# Actuators.net
KiCad netlist of a schematic drawn in Altium Designer
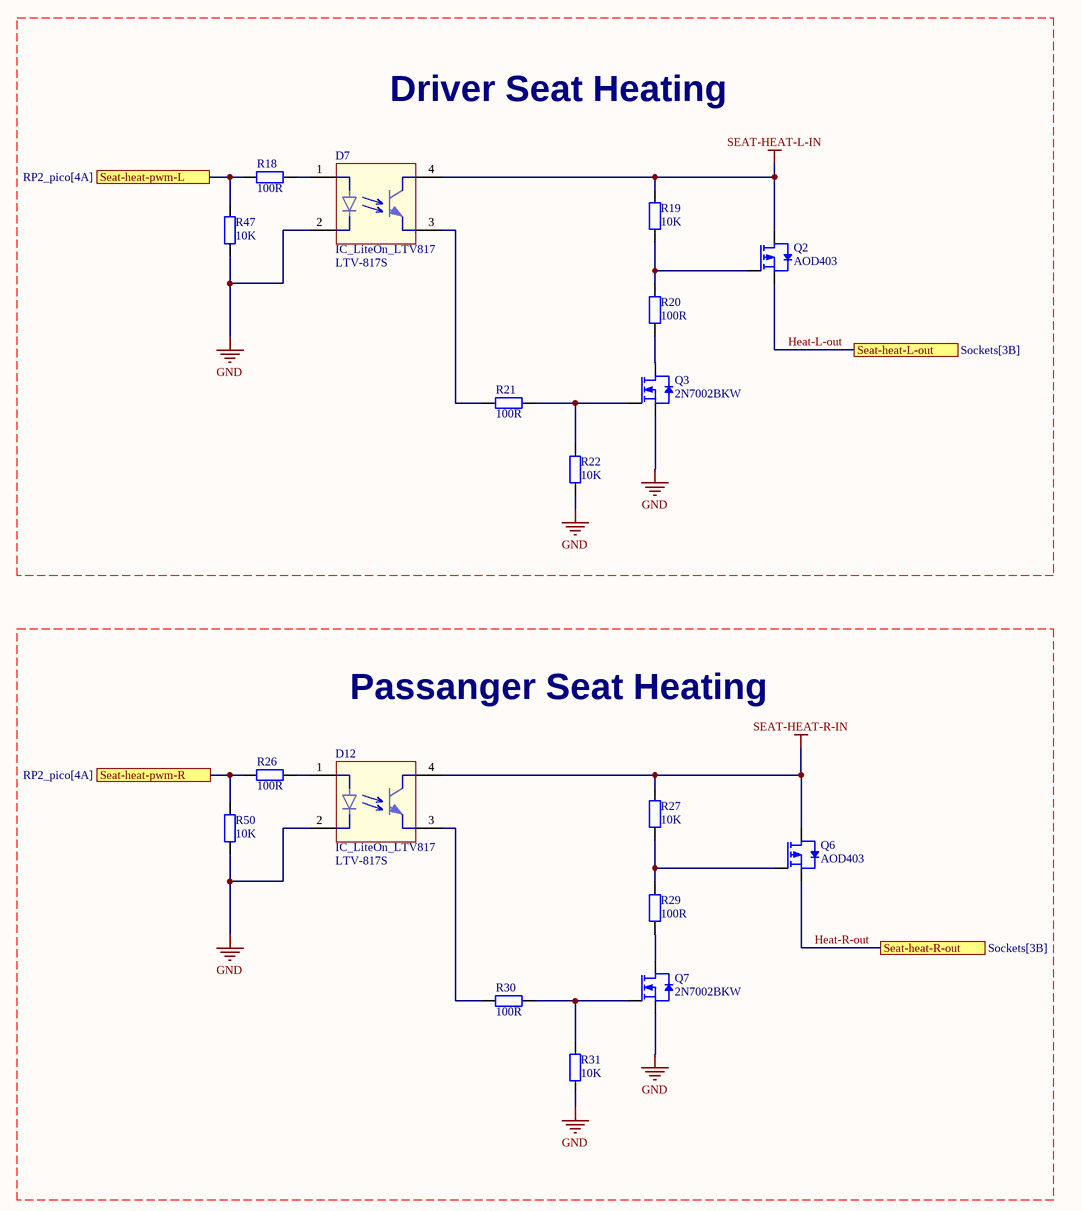
[diagram p0: Actuators.SchDoc, left]
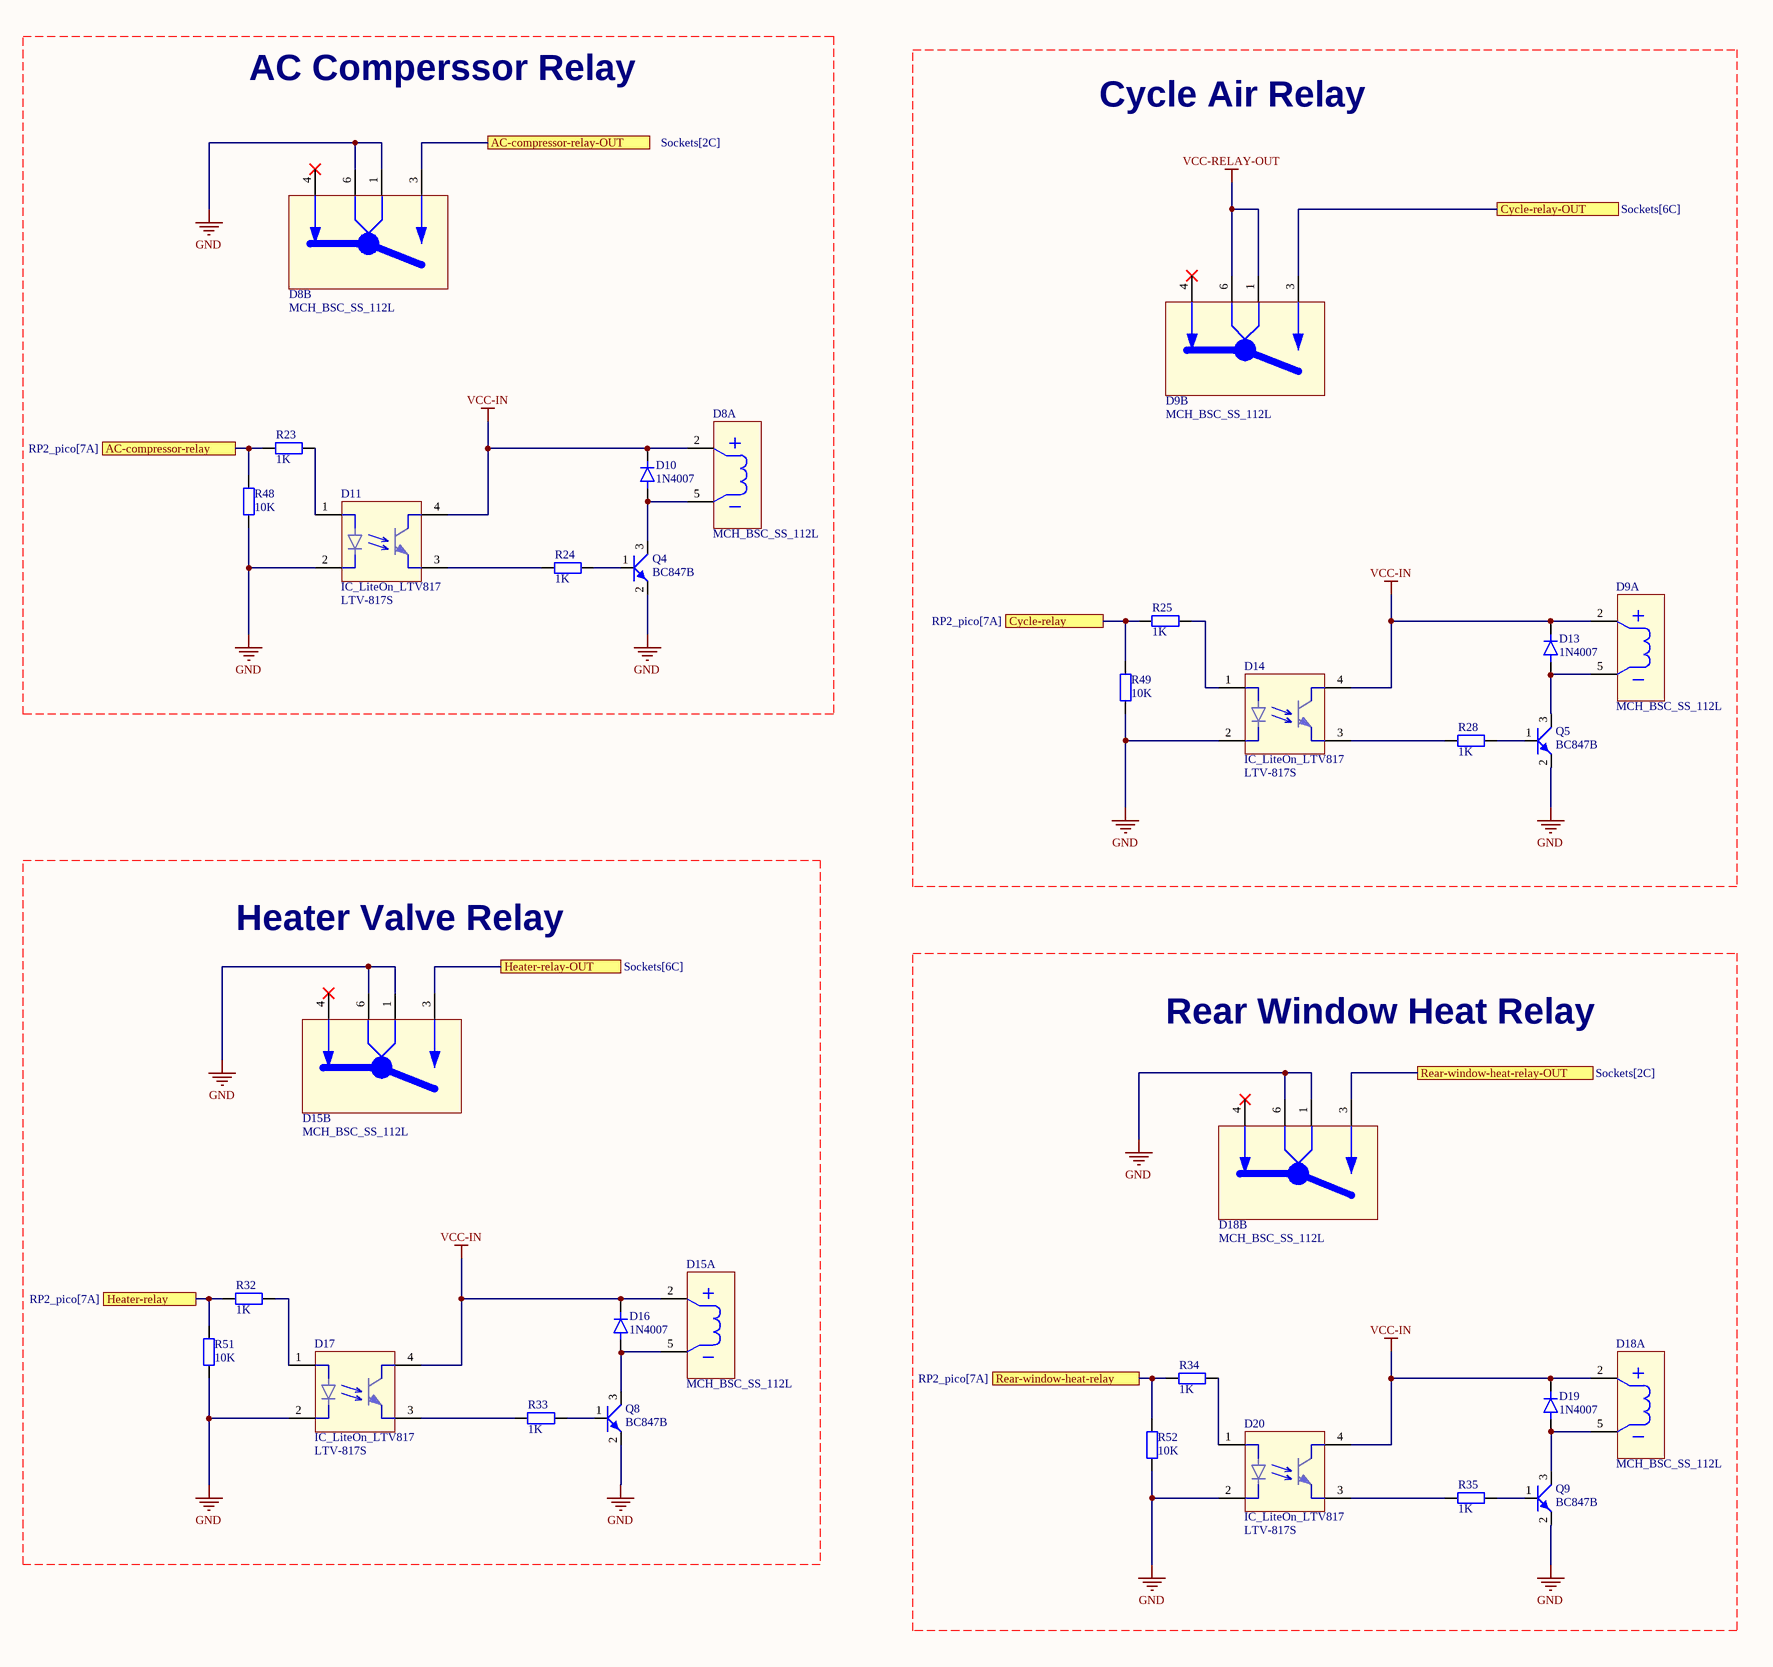
[diagram p1: Actuators.SchDoc, right]

(export (version "E")
  (design (tool "Eeschema 10.0.6"))
  (components
    (comp (ref "D7")
      (value "IC_LiteOn_LTV817")
      (footprint "IC_LiteOn_ LTV-817S")
      (description "Transistor Output Optocouplers Optocoupler Phototrans")
      (fields (field (name "VALUE1") "LTV-817S") (field (name "MANUFACTURER") "Lite-On"))
      (libsource (lib "DSW_Lib") (part "IC_LiteOn_LTV817"))
    )
    (comp (ref "D8")
      (value "MCH_BSC_SS_112L")
      (footprint "MCH_BSC_SS_112L")
      (description "Small relay 6 pins 12V, 2A")
      (fields (field (name "MANUFACTURER") "KJS"))
      (libsource (lib "") (part "MCH_BSC_SS_112L_1"))
    )
    (comp (ref "D9")
      (value "MCH_BSC_SS_112L")
      (footprint "MCH_BSC_SS_112L")
      (description "Small relay 6 pins 12V, 2A")
      (fields (field (name "MANUFACTURER") "KJS"))
      (libsource (lib "") (part "MCH_BSC_SS_112L_2"))
    )
    (comp (ref "D10")
      (value "DIO")
      (footprint "DO-214AC")
      (description "M7 Diode, max 30A")
      (fields (field (name "VALUE1") "1N4007"))
      (libsource (lib "DSW_Lib") (part "DIO"))
    )
    (comp (ref "D11")
      (value "IC_LiteOn_LTV817")
      (footprint "IC_LiteOn_ LTV-817S")
      (description "Transistor Output Optocouplers Optocoupler Phototrans")
      (fields (field (name "VALUE1") "LTV-817S") (field (name "MANUFACTURER") "Lite-On"))
      (libsource (lib "DSW_Lib") (part "IC_LiteOn_LTV817"))
    )
    (comp (ref "D12")
      (value "IC_LiteOn_LTV817")
      (footprint "IC_LiteOn_ LTV-817S")
      (description "Transistor Output Optocouplers Optocoupler Phototrans")
      (fields (field (name "VALUE1") "LTV-817S") (field (name "MANUFACTURER") "Lite-On"))
      (libsource (lib "DSW_Lib") (part "IC_LiteOn_LTV817"))
    )
    (comp (ref "D13")
      (value "DIO")
      (footprint "DO-214AC")
      (description "M7 Diode, max 30A")
      (fields (field (name "VALUE1") "1N4007"))
      (libsource (lib "DSW_Lib") (part "DIO"))
    )
    (comp (ref "D14")
      (value "IC_LiteOn_LTV817")
      (footprint "IC_LiteOn_ LTV-817S")
      (description "Transistor Output Optocouplers Optocoupler Phototrans")
      (fields (field (name "VALUE1") "LTV-817S") (field (name "MANUFACTURER") "Lite-On"))
      (libsource (lib "DSW_Lib") (part "IC_LiteOn_LTV817"))
    )
    (comp (ref "D15")
      (value "MCH_BSC_SS_112L")
      (footprint "MCH_BSC_SS_112L")
      (description "Small relay 6 pins 12V, 2A")
      (fields (field (name "MANUFACTURER") "KJS"))
      (libsource (lib "DSW_Lib") (part "MCH_BSC_SS_112L"))
    )
    (comp (ref "D16")
      (value "DIO")
      (footprint "DO-214AC")
      (description "M7 Diode, max 30A")
      (fields (field (name "VALUE1") "1N4007"))
      (libsource (lib "DSW_Lib") (part "DIO"))
    )
    (comp (ref "D17")
      (value "IC_LiteOn_LTV817")
      (footprint "IC_LiteOn_ LTV-817S")
      (description "Transistor Output Optocouplers Optocoupler Phototrans")
      (fields (field (name "VALUE1") "LTV-817S") (field (name "MANUFACTURER") "Lite-On"))
      (libsource (lib "DSW_Lib") (part "IC_LiteOn_LTV817"))
    )
    (comp (ref "D18")
      (value "MCH_BSC_SS_112L")
      (footprint "MCH_BSC_SS_112L")
      (description "Small relay 6 pins 12V, 2A")
      (fields (field (name "MANUFACTURER") "KJS"))
      (libsource (lib "DSW_Lib") (part "MCH_BSC_SS_112L"))
    )
    (comp (ref "D19")
      (value "DIO")
      (footprint "DO-214AC")
      (description "M7 Diode, max 30A")
      (fields (field (name "VALUE1") "1N4007"))
      (libsource (lib "DSW_Lib") (part "DIO"))
    )
    (comp (ref "D20")
      (value "IC_LiteOn_LTV817")
      (footprint "IC_LiteOn_ LTV-817S")
      (description "Transistor Output Optocouplers Optocoupler Phototrans")
      (fields (field (name "VALUE1") "LTV-817S") (field (name "MANUFACTURER") "Lite-On"))
      (libsource (lib "DSW_Lib") (part "IC_LiteOn_LTV817"))
    )
    (comp (ref "Q2")
      (value "TRS_FETP_123")
      (footprint "TO-252")
      (description "30V P-Channel MOSFET")
      (fields (field (name "VALUE1") "AOD403") (field (name "MANUFACTURER") "Alpha & Omega"))
      (libsource (lib "DSW_Lib") (part "TRS_FETP_123"))
    )
    (comp (ref "Q3")
      (value "TRS_FETN_123")
      (footprint "SOT65P210X110-3N")
      (description "NXP - 2N7002BKW - MOSFET, N CH, 60V, 0.31A, SOT323")
      (fields (field (name "VALUE1") "2N7002BKW") (field (name "MANUFACTURER") "NXP"))
      (libsource (lib "DSW_Lib") (part "TRS_FETN_123"))
    )
    (comp (ref "Q4")
      (value "TRS_NPN_123")
      (footprint "SOT23")
      (description "Bipolar Transistors - BJT NPN 45V 100mA")
      (fields (field (name "VALUE1") "BC847B") (field (name "MANUFACTURER") "NXP"))
      (libsource (lib "DSW_Lib") (part "TRS_NPN_123"))
    )
    (comp (ref "Q5")
      (value "TRS_NPN_123")
      (footprint "SOT23")
      (description "Bipolar Transistors - BJT NPN 45V 100mA")
      (fields (field (name "VALUE1") "BC847B") (field (name "MANUFACTURER") "NXP"))
      (libsource (lib "DSW_Lib") (part "TRS_NPN_123"))
    )
    (comp (ref "Q6")
      (value "TRS_FETP_123")
      (footprint "TO-252")
      (description "30V P-Channel MOSFET")
      (fields (field (name "VALUE1") "AOD403") (field (name "MANUFACTURER") "Alpha & Omega"))
      (libsource (lib "DSW_Lib") (part "TRS_FETP_123"))
    )
    (comp (ref "Q7")
      (value "TRS_FETN_123")
      (footprint "SOT65P210X110-3N")
      (description "NXP - 2N7002BKW - MOSFET, N CH, 60V, 0.31A, SOT323")
      (fields (field (name "VALUE1") "2N7002BKW") (field (name "MANUFACTURER") "NXP"))
      (libsource (lib "DSW_Lib") (part "TRS_FETN_123"))
    )
    (comp (ref "Q8")
      (value "TRS_NPN_123")
      (footprint "SOT23")
      (description "Bipolar Transistors - BJT NPN 45V 100mA")
      (fields (field (name "VALUE1") "BC847B") (field (name "MANUFACTURER") "NXP"))
      (libsource (lib "DSW_Lib") (part "TRS_NPN_123"))
    )
    (comp (ref "Q9")
      (value "TRS_NPN_123")
      (footprint "SOT23")
      (description "Bipolar Transistors - BJT NPN 45V 100mA")
      (fields (field (name "VALUE1") "BC847B") (field (name "MANUFACTURER") "NXP"))
      (libsource (lib "DSW_Lib") (part "TRS_NPN_123"))
    )
    (comp (ref "R18")
      (value "RES")
      (footprint "RESC2012X60N")
      (description "RESISTOR, 0805, 100R, 1%, SMD")
      (fields (field (name "VALUE1") "100R") (field (name "MANUFACTURER") "Yageo"))
      (libsource (lib "") (part "RES_3"))
    )
    (comp (ref "R19")
      (value "RES")
      (footprint "RESC2012X60N")
      (description "RESISTOR, 0805, 10K, 1%, SMD")
      (fields (field (name "VALUE1") "10K") (field (name "MANUFACTURER") "Yageo"))
      (libsource (lib "DSW_Lib") (part "RES"))
    )
    (comp (ref "R20")
      (value "RES")
      (footprint "RESC2012X60N")
      (description "RESISTOR, 0805, 100R, 1%, SMD")
      (fields (field (name "VALUE1") "100R") (field (name "MANUFACTURER") "Yageo"))
      (libsource (lib "") (part "RES_2"))
    )
    (comp (ref "R21")
      (value "RES")
      (footprint "RESC2012X60N")
      (description "RESISTOR, 0805, 100R, 1%, SMD")
      (fields (field (name "VALUE1") "100R") (field (name "MANUFACTURER") "Yageo"))
      (libsource (lib "") (part "RES_3"))
    )
    (comp (ref "R22")
      (value "RES")
      (footprint "RESC2012X60N")
      (description "RESISTOR, 0805, 10K, 1%, SMD")
      (fields (field (name "VALUE1") "10K") (field (name "MANUFACTURER") "Yageo"))
      (libsource (lib "") (part "RES_2"))
    )
    (comp (ref "R23")
      (value "RES")
      (footprint "RESC2012X60N")
      (description "RESISTOR, 0805, 1K, 1%, SMD")
      (fields (field (name "VALUE1") "1K") (field (name "MANUFACTURER") "Yageo"))
      (libsource (lib "") (part "RES_1"))
    )
    (comp (ref "R24")
      (value "RES")
      (footprint "RESC2012X60N")
      (description "RESISTOR, 0805, 1K, 1%, SMD")
      (fields (field (name "VALUE1") "1K") (field (name "MANUFACTURER") "Yageo"))
      (libsource (lib "") (part "RES_1"))
    )
    (comp (ref "R25")
      (value "RES")
      (footprint "RESC2012X60N")
      (description "RESISTOR, 0805, 1K, 1%, SMD")
      (fields (field (name "VALUE1") "1K") (field (name "MANUFACTURER") "Yageo"))
      (libsource (lib "") (part "RES_1"))
    )
    (comp (ref "R26")
      (value "RES")
      (footprint "RESC2012X60N")
      (description "RESISTOR, 0805, 100R, 1%, SMD")
      (fields (field (name "VALUE1") "100R") (field (name "MANUFACTURER") "Yageo"))
      (libsource (lib "") (part "RES_3"))
    )
    (comp (ref "R27")
      (value "RES")
      (footprint "RESC2012X60N")
      (description "RESISTOR, 0805, 10K, 1%, SMD")
      (fields (field (name "VALUE1") "10K") (field (name "MANUFACTURER") "Yageo"))
      (libsource (lib "DSW_Lib") (part "RES"))
    )
    (comp (ref "R28")
      (value "RES")
      (footprint "RESC2012X60N")
      (description "RESISTOR, 0805, 1K, 1%, SMD")
      (fields (field (name "VALUE1") "1K") (field (name "MANUFACTURER") "Yageo"))
      (libsource (lib "") (part "RES_1"))
    )
    (comp (ref "R29")
      (value "RES")
      (footprint "RESC2012X60N")
      (description "RESISTOR, 0805, 100R, 1%, SMD")
      (fields (field (name "VALUE1") "100R") (field (name "MANUFACTURER") "Yageo"))
      (libsource (lib "") (part "RES_2"))
    )
    (comp (ref "R30")
      (value "RES")
      (footprint "RESC2012X60N")
      (description "RESISTOR, 0805, 100R, 1%, SMD")
      (fields (field (name "VALUE1") "100R") (field (name "MANUFACTURER") "Yageo"))
      (libsource (lib "") (part "RES_1"))
    )
    (comp (ref "R31")
      (value "RES")
      (footprint "RESC2012X60N")
      (description "RESISTOR, 0805, 10K, 1%, SMD")
      (fields (field (name "VALUE1") "10K") (field (name "MANUFACTURER") "Yageo"))
      (libsource (lib "") (part "RES_2"))
    )
    (comp (ref "R32")
      (value "RES")
      (footprint "RESC2012X60N")
      (description "RESISTOR, 0805, 1K, 1%, SMD")
      (fields (field (name "VALUE1") "1K") (field (name "MANUFACTURER") "Yageo"))
      (libsource (lib "") (part "RES_1"))
    )
    (comp (ref "R33")
      (value "RES")
      (footprint "RESC2012X60N")
      (description "RESISTOR, 0805, 1K, 1%, SMD")
      (fields (field (name "VALUE1") "1K") (field (name "MANUFACTURER") "Yageo"))
      (libsource (lib "") (part "RES_1"))
    )
    (comp (ref "R34")
      (value "RES")
      (footprint "RESC2012X60N")
      (description "RESISTOR, 0805, 1K, 1%, SMD")
      (fields (field (name "VALUE1") "1K") (field (name "MANUFACTURER") "Yageo"))
      (libsource (lib "") (part "RES_1"))
    )
    (comp (ref "R35")
      (value "RES")
      (footprint "RESC2012X60N")
      (description "RESISTOR, 0805, 1K, 1%, SMD")
      (fields (field (name "VALUE1") "1K") (field (name "MANUFACTURER") "Yageo"))
      (libsource (lib "") (part "RES_1"))
    )
    (comp (ref "R47")
      (value "RES")
      (footprint "RESC2012X60N")
      (description "RESISTOR, 0805, 10K, 1%, SMD")
      (fields (field (name "VALUE1") "10K") (field (name "MANUFACTURER") "Yageo"))
      (libsource (lib "DSW_Lib") (part "RES"))
    )
    (comp (ref "R48")
      (value "RES")
      (footprint "RESC2012X60N")
      (description "RESISTOR, 0805, 10K, 1%, SMD")
      (fields (field (name "VALUE1") "10K") (field (name "MANUFACTURER") "Yageo"))
      (libsource (lib "DSW_Lib") (part "RES"))
    )
    (comp (ref "R49")
      (value "RES")
      (footprint "RESC2012X60N")
      (description "RESISTOR, 0805, 10K, 1%, SMD")
      (fields (field (name "VALUE1") "10K") (field (name "MANUFACTURER") "Yageo"))
      (libsource (lib "DSW_Lib") (part "RES"))
    )
    (comp (ref "R50")
      (value "RES")
      (footprint "RESC2012X60N")
      (description "RESISTOR, 0805, 10K, 1%, SMD")
      (fields (field (name "VALUE1") "10K") (field (name "MANUFACTURER") "Yageo"))
      (libsource (lib "DSW_Lib") (part "RES"))
    )
    (comp (ref "R51")
      (value "RES")
      (footprint "RESC2012X60N")
      (description "RESISTOR, 0805, 10K, 1%, SMD")
      (fields (field (name "VALUE1") "10K") (field (name "MANUFACTURER") "Yageo"))
      (libsource (lib "DSW_Lib") (part "RES"))
    )
    (comp (ref "R52")
      (value "RES")
      (footprint "RESC2012X60N")
      (description "RESISTOR, 0805, 10K, 1%, SMD")
      (fields (field (name "VALUE1") "10K") (field (name "MANUFACTURER") "Yageo"))
      (libsource (lib "DSW_Lib") (part "RES"))
    )
  )
  (nets
    (net (code "1") (name "/AC-compressor-relay") (class "Default")
      (node (ref "R23") (pin "2") (pinfunction "2_2") (pintype "passive"))
      (node (ref "R48") (pin "1") (pinfunction "1_1") (pintype "passive"))
    )
    (net (code "2") (name "/AC-compressor-relay-OUT") (class "Default")
      (node (ref "D8") (pin "3") (pinfunction "3_3") (pintype "passive"))
    )
    (net (code "3") (name "/Cycle-relay") (class "Default")
      (node (ref "R25") (pin "2") (pinfunction "2_2") (pintype "passive"))
      (node (ref "R49") (pin "1") (pinfunction "1_1") (pintype "passive"))
    )
    (net (code "4") (name "/Cycle-relay-OUT") (class "Default")
      (node (ref "D9") (pin "3") (pinfunction "3_3") (pintype "passive"))
    )
    (net (code "5") (name "/Heat-L-out") (class "Default")
      (node (ref "Q2") (pin "2") (pinfunction "S_2") (pintype "passive"))
    )
    (net (code "6") (name "/Heat-R-out") (class "Default")
      (node (ref "Q6") (pin "2") (pinfunction "S_2") (pintype "passive"))
    )
    (net (code "7") (name "/Heater-relay") (class "Default")
      (node (ref "R32") (pin "2") (pinfunction "2_2") (pintype "passive"))
      (node (ref "R51") (pin "1") (pinfunction "1_1") (pintype "passive"))
    )
    (net (code "8") (name "/Heater-relay-OUT") (class "Default")
      (node (ref "D15") (pin "3") (pinfunction "3_3") (pintype "passive"))
    )
    (net (code "9") (name "/Rear-window-heat-relay") (class "Default")
      (node (ref "R34") (pin "2") (pinfunction "2_2") (pintype "passive"))
      (node (ref "R52") (pin "1") (pinfunction "1_1") (pintype "passive"))
    )
    (net (code "10") (name "/Rear-window-heat-relay-OUT") (class "Default")
      (node (ref "D18") (pin "3") (pinfunction "3_3") (pintype "passive"))
    )
    (net (code "11") (name "/Seat-heat-pwm-L") (class "Default")
      (node (ref "R18") (pin "1") (pinfunction "1_1") (pintype "passive"))
      (node (ref "R47") (pin "1") (pinfunction "1_1") (pintype "passive"))
    )
    (net (code "12") (name "/Seat-heat-pwm-R") (class "Default")
      (node (ref "R26") (pin "1") (pinfunction "1_1") (pintype "passive"))
      (node (ref "R50") (pin "1") (pinfunction "1_1") (pintype "passive"))
    )
    (net (code "13") (name "GND") (class "Default")
      (node (ref "D11") (pin "2") (pinfunction "2_2") (pintype "passive"))
      (node (ref "D12") (pin "2") (pinfunction "2_2") (pintype "passive"))
      (node (ref "D14") (pin "2") (pinfunction "2_2") (pintype "passive"))
      (node (ref "D15") (pin "1") (pinfunction "1_1") (pintype "passive"))
      (node (ref "D15") (pin "6") (pinfunction "6_6") (pintype "passive"))
      (node (ref "D17") (pin "2") (pinfunction "2_2") (pintype "passive"))
      (node (ref "D18") (pin "1") (pinfunction "1_1") (pintype "passive"))
      (node (ref "D18") (pin "6") (pinfunction "6_6") (pintype "passive"))
      (node (ref "D20") (pin "2") (pinfunction "2_2") (pintype "passive"))
      (node (ref "D7") (pin "2") (pinfunction "2_2") (pintype "passive"))
      (node (ref "D8") (pin "1") (pinfunction "1_1") (pintype "passive"))
      (node (ref "D8") (pin "6") (pinfunction "6_6") (pintype "passive"))
      (node (ref "Q3") (pin "2") (pinfunction "S_2") (pintype "passive"))
      (node (ref "Q4") (pin "2") (pinfunction "E_2") (pintype "passive"))
      (node (ref "Q5") (pin "2") (pinfunction "E_2") (pintype "passive"))
      (node (ref "Q7") (pin "2") (pinfunction "S_2") (pintype "passive"))
      (node (ref "Q8") (pin "2") (pinfunction "E_2") (pintype "passive"))
      (node (ref "Q9") (pin "2") (pinfunction "E_2") (pintype "passive"))
      (node (ref "R22") (pin "1") (pinfunction "1_1") (pintype "passive"))
      (node (ref "R31") (pin "1") (pinfunction "1_1") (pintype "passive"))
      (node (ref "R47") (pin "2") (pinfunction "2_2") (pintype "passive"))
      (node (ref "R48") (pin "2") (pinfunction "2_2") (pintype "passive"))
      (node (ref "R49") (pin "2") (pinfunction "2_2") (pintype "passive"))
      (node (ref "R50") (pin "2") (pinfunction "2_2") (pintype "passive"))
      (node (ref "R51") (pin "2") (pinfunction "2_2") (pintype "passive"))
      (node (ref "R52") (pin "2") (pinfunction "2_2") (pintype "passive"))
    )
    (net (code "14") (name "Net-(D7-Pad1)") (class "Default")
      (node (ref "D7") (pin "1") (pinfunction "1_1") (pintype "passive"))
      (node (ref "R18") (pin "2") (pinfunction "2_2") (pintype "passive"))
    )
    (net (code "15") (name "Net-(D7-Pad3)") (class "Default")
      (node (ref "D7") (pin "3") (pinfunction "3_3") (pintype "passive"))
      (node (ref "R21") (pin "1") (pinfunction "1_1") (pintype "passive"))
    )
    (net (code "16") (name "Net-(D10-A)") (class "Default")
      (node (ref "D10") (pin "1") (pinfunction "A_1") (pintype "passive"))
      (node (ref "D8") (pin "5") (pinfunction "5_5") (pintype "passive"))
      (node (ref "Q4") (pin "3") (pinfunction "C_3") (pintype "passive"))
    )
    (net (code "17") (name "Net-(D11-Pad1)") (class "Default")
      (node (ref "D11") (pin "1") (pinfunction "1_1") (pintype "passive"))
      (node (ref "R23") (pin "1") (pinfunction "1_1") (pintype "passive"))
    )
    (net (code "18") (name "Net-(D11-Pad3)") (class "Default")
      (node (ref "D11") (pin "3") (pinfunction "3_3") (pintype "passive"))
      (node (ref "R24") (pin "2") (pinfunction "2_2") (pintype "passive"))
    )
    (net (code "19") (name "Net-(D12-Pad1)") (class "Default")
      (node (ref "D12") (pin "1") (pinfunction "1_1") (pintype "passive"))
      (node (ref "R26") (pin "2") (pinfunction "2_2") (pintype "passive"))
    )
    (net (code "20") (name "Net-(D12-Pad3)") (class "Default")
      (node (ref "D12") (pin "3") (pinfunction "3_3") (pintype "passive"))
      (node (ref "R30") (pin "2") (pinfunction "2_2") (pintype "passive"))
    )
    (net (code "21") (name "Net-(D13-A)") (class "Default")
      (node (ref "D13") (pin "1") (pinfunction "A_1") (pintype "passive"))
      (node (ref "D9") (pin "5") (pinfunction "5_5") (pintype "passive"))
      (node (ref "Q5") (pin "3") (pinfunction "C_3") (pintype "passive"))
    )
    (net (code "22") (name "Net-(D14-Pad1)") (class "Default")
      (node (ref "D14") (pin "1") (pinfunction "1_1") (pintype "passive"))
      (node (ref "R25") (pin "1") (pinfunction "1_1") (pintype "passive"))
    )
    (net (code "23") (name "Net-(D14-Pad3)") (class "Default")
      (node (ref "D14") (pin "3") (pinfunction "3_3") (pintype "passive"))
      (node (ref "R28") (pin "2") (pinfunction "2_2") (pintype "passive"))
    )
    (net (code "24") (name "Net-(D16-A)") (class "Default")
      (node (ref "D15") (pin "5") (pinfunction "5_5") (pintype "passive"))
      (node (ref "D16") (pin "1") (pinfunction "A_1") (pintype "passive"))
      (node (ref "Q8") (pin "3") (pinfunction "C_3") (pintype "passive"))
    )
    (net (code "25") (name "Net-(D17-Pad1)") (class "Default")
      (node (ref "D17") (pin "1") (pinfunction "1_1") (pintype "passive"))
      (node (ref "R32") (pin "1") (pinfunction "1_1") (pintype "passive"))
    )
    (net (code "26") (name "Net-(D17-Pad3)") (class "Default")
      (node (ref "D17") (pin "3") (pinfunction "3_3") (pintype "passive"))
      (node (ref "R33") (pin "2") (pinfunction "2_2") (pintype "passive"))
    )
    (net (code "27") (name "Net-(D19-A)") (class "Default")
      (node (ref "D18") (pin "5") (pinfunction "5_5") (pintype "passive"))
      (node (ref "D19") (pin "1") (pinfunction "A_1") (pintype "passive"))
      (node (ref "Q9") (pin "3") (pinfunction "C_3") (pintype "passive"))
    )
    (net (code "28") (name "Net-(D20-Pad1)") (class "Default")
      (node (ref "D20") (pin "1") (pinfunction "1_1") (pintype "passive"))
      (node (ref "R34") (pin "1") (pinfunction "1_1") (pintype "passive"))
    )
    (net (code "29") (name "Net-(D20-Pad3)") (class "Default")
      (node (ref "D20") (pin "3") (pinfunction "3_3") (pintype "passive"))
      (node (ref "R35") (pin "2") (pinfunction "2_2") (pintype "passive"))
    )
    (net (code "30") (name "Net-(Q2-G)") (class "Default")
      (node (ref "Q2") (pin "1") (pinfunction "G_1") (pintype "passive"))
      (node (ref "R19") (pin "2") (pinfunction "2_2") (pintype "passive"))
      (node (ref "R20") (pin "2") (pinfunction "2_2") (pintype "passive"))
    )
    (net (code "31") (name "Net-(Q3-D)") (class "Default")
      (node (ref "Q3") (pin "3") (pinfunction "D_3") (pintype "passive"))
      (node (ref "R20") (pin "1") (pinfunction "1_1") (pintype "passive"))
    )
    (net (code "32") (name "Net-(Q3-G)") (class "Default")
      (node (ref "Q3") (pin "1") (pinfunction "G_1") (pintype "passive"))
      (node (ref "R21") (pin "2") (pinfunction "2_2") (pintype "passive"))
      (node (ref "R22") (pin "2") (pinfunction "2_2") (pintype "passive"))
    )
    (net (code "33") (name "Net-(Q4-B)") (class "Default")
      (node (ref "Q4") (pin "1") (pinfunction "B_1") (pintype "passive"))
      (node (ref "R24") (pin "1") (pinfunction "1_1") (pintype "passive"))
    )
    (net (code "34") (name "Net-(Q5-B)") (class "Default")
      (node (ref "Q5") (pin "1") (pinfunction "B_1") (pintype "passive"))
      (node (ref "R28") (pin "1") (pinfunction "1_1") (pintype "passive"))
    )
    (net (code "35") (name "Net-(Q6-G)") (class "Default")
      (node (ref "Q6") (pin "1") (pinfunction "G_1") (pintype "passive"))
      (node (ref "R27") (pin "2") (pinfunction "2_2") (pintype "passive"))
      (node (ref "R29") (pin "2") (pinfunction "2_2") (pintype "passive"))
    )
    (net (code "36") (name "Net-(Q7-D)") (class "Default")
      (node (ref "Q7") (pin "3") (pinfunction "D_3") (pintype "passive"))
      (node (ref "R29") (pin "1") (pinfunction "1_1") (pintype "passive"))
    )
    (net (code "37") (name "Net-(Q7-G)") (class "Default")
      (node (ref "Q7") (pin "1") (pinfunction "G_1") (pintype "passive"))
      (node (ref "R30") (pin "1") (pinfunction "1_1") (pintype "passive"))
      (node (ref "R31") (pin "2") (pinfunction "2_2") (pintype "passive"))
    )
    (net (code "38") (name "Net-(Q8-B)") (class "Default")
      (node (ref "Q8") (pin "1") (pinfunction "B_1") (pintype "passive"))
      (node (ref "R33") (pin "1") (pinfunction "1_1") (pintype "passive"))
    )
    (net (code "39") (name "Net-(Q9-B)") (class "Default")
      (node (ref "Q9") (pin "1") (pinfunction "B_1") (pintype "passive"))
      (node (ref "R35") (pin "1") (pinfunction "1_1") (pintype "passive"))
    )
    (net (code "40") (name "SEAT-HEAT-L-IN") (class "Default")
      (node (ref "D7") (pin "4") (pinfunction "4_4") (pintype "passive"))
      (node (ref "Q2") (pin "3") (pinfunction "D_3") (pintype "passive"))
      (node (ref "R19") (pin "1") (pinfunction "1_1") (pintype "passive"))
    )
    (net (code "41") (name "SEAT-HEAT-R-IN") (class "Default")
      (node (ref "D12") (pin "4") (pinfunction "4_4") (pintype "passive"))
      (node (ref "Q6") (pin "3") (pinfunction "D_3") (pintype "passive"))
      (node (ref "R27") (pin "1") (pinfunction "1_1") (pintype "passive"))
    )
    (net (code "42") (name "VCC-IN") (class "Default")
      (node (ref "D10") (pin "2") (pinfunction "K_2") (pintype "passive"))
      (node (ref "D11") (pin "4") (pinfunction "4_4") (pintype "passive"))
      (node (ref "D13") (pin "2") (pinfunction "K_2") (pintype "passive"))
      (node (ref "D14") (pin "4") (pinfunction "4_4") (pintype "passive"))
      (node (ref "D15") (pin "2") (pinfunction "2_2") (pintype "passive"))
      (node (ref "D16") (pin "2") (pinfunction "K_2") (pintype "passive"))
      (node (ref "D17") (pin "4") (pinfunction "4_4") (pintype "passive"))
      (node (ref "D18") (pin "2") (pinfunction "2_2") (pintype "passive"))
      (node (ref "D19") (pin "2") (pinfunction "K_2") (pintype "passive"))
      (node (ref "D20") (pin "4") (pinfunction "4_4") (pintype "passive"))
      (node (ref "D8") (pin "2") (pinfunction "2_2") (pintype "passive"))
      (node (ref "D9") (pin "2") (pinfunction "2_2") (pintype "passive"))
    )
    (net (code "43") (name "VCC-RELAY-OUT") (class "Default")
      (node (ref "D9") (pin "1") (pinfunction "1_1") (pintype "passive"))
      (node (ref "D9") (pin "6") (pinfunction "6_6") (pintype "passive"))
    )
    (net (code "44") (name "unconnected-(D8-Pad4)") (class "Default")
      (node (ref "D8") (pin "4") (pinfunction "4_4") (pintype "passive+no_connect"))
    )
    (net (code "45") (name "unconnected-(D9-Pad4)") (class "Default")
      (node (ref "D9") (pin "4") (pinfunction "4_4") (pintype "passive+no_connect"))
    )
    (net (code "46") (name "unconnected-(D15-Pad4)") (class "Default")
      (node (ref "D15") (pin "4") (pinfunction "4_4") (pintype "passive+no_connect"))
    )
    (net (code "47") (name "unconnected-(D18-Pad4)") (class "Default")
      (node (ref "D18") (pin "4") (pinfunction "4_4") (pintype "passive+no_connect"))
    )
  )
)
